# wiring.net
KiCad netlist of a schematic drawn in EAGLE
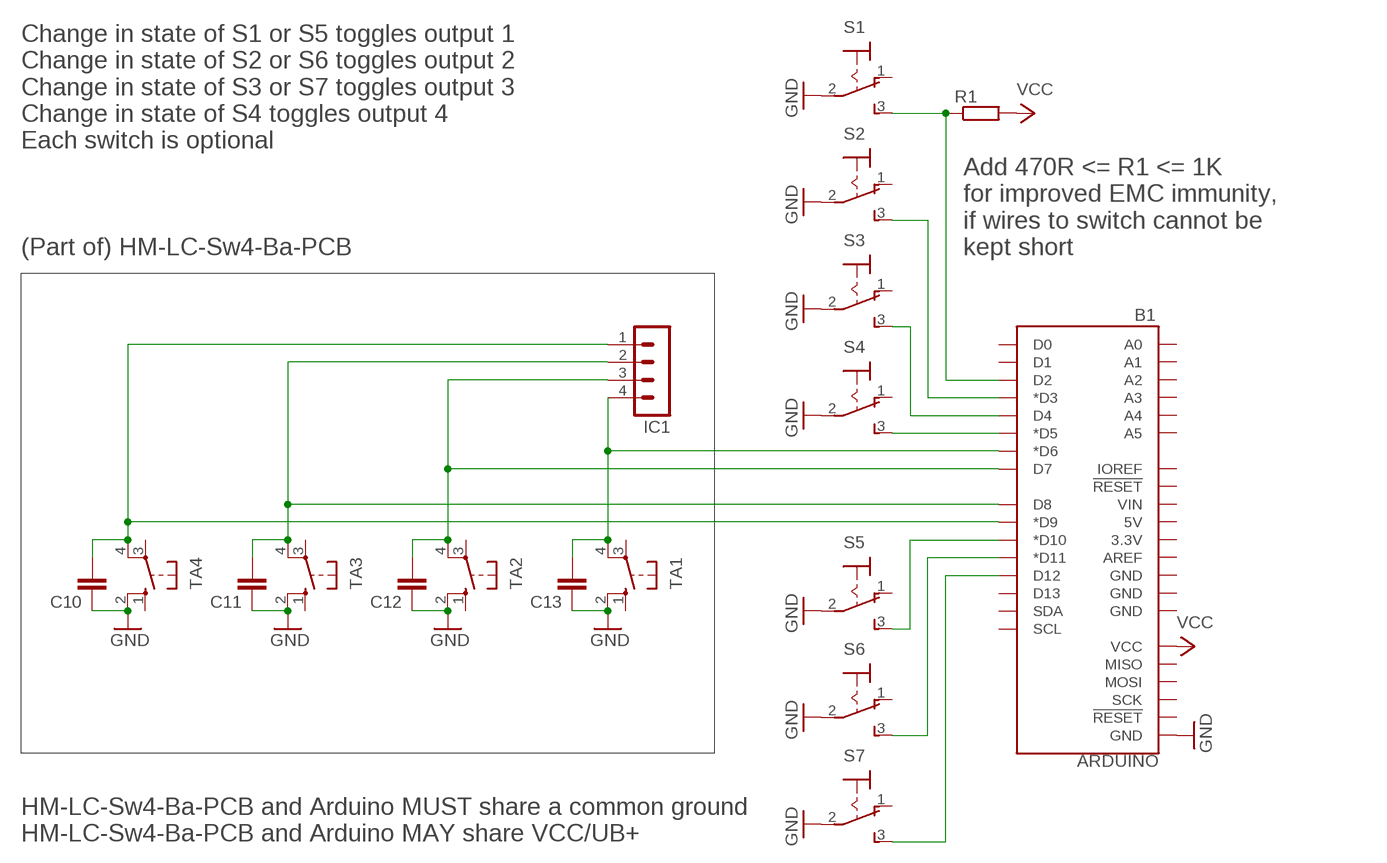
[diagram p0: schematic, sheet 1]

(export (version "E")
  (design (tool "Eeschema 10.0.6"))
  (components
    (comp (ref "B1")
      (value "ARDUINO")
      (footprint "eagle-import:ARDUINO_R3")
      (libsource (lib "eagle-import") (part "ARDUINO_UNO_R3"))
    )
    (comp (ref "C10")
      (value "C2,5-3")
      (footprint "eagle-import:C2.5-3")
      (libsource (lib "eagle-import") (part "C2,5-3"))
    )
    (comp (ref "C11")
      (value "C2,5-3")
      (footprint "eagle-import:C2.5-3")
      (libsource (lib "eagle-import") (part "C2,5-3"))
    )
    (comp (ref "C12")
      (value "C2,5-3")
      (footprint "eagle-import:C2.5-3")
      (libsource (lib "eagle-import") (part "C2,5-3"))
    )
    (comp (ref "C13")
      (value "C2,5-3")
      (footprint "eagle-import:C2.5-3")
      (libsource (lib "eagle-import") (part "C2,5-3"))
    )
    (comp (ref "IC1")
      (value "MA04-1")
      (footprint "eagle-import:MA04-1")
      (libsource (lib "eagle-import") (part "MA04-1"))
    )
    (comp (ref "R1")
      (value "R-EU_0204/5")
      (footprint "eagle-import:0204_5")
      (libsource (lib "eagle-import") (part "R-EU_0204/5"))
    )
    (comp (ref "S1")
      (value "320-916")
      (footprint "eagle-import:320-916")
      (libsource (lib "eagle-import") (part "320-916"))
    )
    (comp (ref "S2")
      (value "320-916")
      (footprint "eagle-import:320-916")
      (libsource (lib "eagle-import") (part "320-916"))
    )
    (comp (ref "S3")
      (value "320-916")
      (footprint "eagle-import:320-916")
      (libsource (lib "eagle-import") (part "320-916"))
    )
    (comp (ref "S4")
      (value "320-916")
      (footprint "eagle-import:320-916")
      (libsource (lib "eagle-import") (part "320-916"))
    )
    (comp (ref "S5")
      (value "320-916")
      (footprint "eagle-import:320-916")
      (libsource (lib "eagle-import") (part "320-916"))
    )
    (comp (ref "S6")
      (value "320-916")
      (footprint "eagle-import:320-916")
      (libsource (lib "eagle-import") (part "320-916"))
    )
    (comp (ref "S7")
      (value "320-916")
      (footprint "eagle-import:320-916")
      (libsource (lib "eagle-import") (part "320-916"))
    )
    (comp (ref "TA1")
      (value "10-XX")
      (footprint "eagle-import:B3F-10XX")
      (fields (field (name "MPN") "B3F-1000"))
      (libsource (lib "eagle-import") (part "10-XX"))
    )
    (comp (ref "TA2")
      (value "10-XX")
      (footprint "eagle-import:B3F-10XX")
      (fields (field (name "MPN") "B3F-1000"))
      (libsource (lib "eagle-import") (part "10-XX"))
    )
    (comp (ref "TA3")
      (value "10-XX")
      (footprint "eagle-import:B3F-10XX")
      (fields (field (name "MPN") "B3F-1000"))
      (libsource (lib "eagle-import") (part "10-XX"))
    )
    (comp (ref "TA4")
      (value "10-XX")
      (footprint "eagle-import:B3F-10XX")
      (fields (field (name "MPN") "B3F-1000"))
      (libsource (lib "eagle-import") (part "10-XX"))
    )
  )
  (nets
    (net (code "1") (name "GND") (class "Default")
      (node (ref "B1") (pin "GND@1") (pinfunction "GND_GND@1") (pintype "bidirectional"))
      (node (ref "C10") (pin "1") (pinfunction "1_1") (pintype "passive"))
      (node (ref "C11") (pin "1") (pinfunction "1_1") (pintype "passive"))
      (node (ref "C12") (pin "1") (pinfunction "1_1") (pintype "passive"))
      (node (ref "C13") (pin "1") (pinfunction "1_1") (pintype "passive"))
      (node (ref "S1") (pin "2") (pinfunction "P_2") (pintype "passive"))
      (node (ref "S2") (pin "2") (pinfunction "P_2") (pintype "passive"))
      (node (ref "S3") (pin "2") (pinfunction "P_2") (pintype "passive"))
      (node (ref "S4") (pin "2") (pinfunction "P_2") (pintype "passive"))
      (node (ref "S5") (pin "2") (pinfunction "P_2") (pintype "passive"))
      (node (ref "S6") (pin "2") (pinfunction "P_2") (pintype "passive"))
      (node (ref "S7") (pin "2") (pinfunction "P_2") (pintype "passive"))
      (node (ref "TA1") (pin "2") (pinfunction "S1_2") (pintype "passive"))
      (node (ref "TA2") (pin "2") (pinfunction "S1_2") (pintype "passive"))
      (node (ref "TA3") (pin "2") (pinfunction "S1_2") (pintype "passive"))
      (node (ref "TA4") (pin "2") (pinfunction "S1_2") (pintype "passive"))
    )
    (net (code "2") (name "Net-(B1-*D3)") (class "Default")
      (node (ref "B1") (pin "D3") (pinfunction "*D3_D3") (pintype "bidirectional"))
      (node (ref "S2") (pin "3") (pinfunction "S_3") (pintype "passive"))
    )
    (net (code "3") (name "Net-(B1-*D5)") (class "Default")
      (node (ref "B1") (pin "D5") (pinfunction "*D5_D5") (pintype "bidirectional"))
      (node (ref "S4") (pin "3") (pinfunction "S_3") (pintype "passive"))
    )
    (net (code "4") (name "Net-(B1-*D6)") (class "Default")
      (node (ref "B1") (pin "D6") (pinfunction "*D6_D6") (pintype "bidirectional"))
      (node (ref "C13") (pin "2") (pinfunction "2_2") (pintype "passive"))
      (node (ref "IC1") (pin "4") (pinfunction "4_4") (pintype "passive"))
      (node (ref "TA1") (pin "4") (pinfunction "P1_4") (pintype "passive"))
    )
    (net (code "5") (name "Net-(B1-*D9)") (class "Default")
      (node (ref "B1") (pin "D9") (pinfunction "*D9_D9") (pintype "bidirectional"))
      (node (ref "C10") (pin "2") (pinfunction "2_2") (pintype "passive"))
      (node (ref "IC1") (pin "1") (pinfunction "1_1") (pintype "passive"))
      (node (ref "TA4") (pin "4") (pinfunction "P1_4") (pintype "passive"))
    )
    (net (code "6") (name "Net-(B1-*D10)") (class "Default")
      (node (ref "B1") (pin "D10") (pinfunction "*D10_D10") (pintype "bidirectional"))
      (node (ref "S5") (pin "3") (pinfunction "S_3") (pintype "passive"))
    )
    (net (code "7") (name "Net-(B1-*D11)") (class "Default")
      (node (ref "B1") (pin "D11") (pinfunction "*D11_D11") (pintype "bidirectional"))
      (node (ref "S6") (pin "3") (pinfunction "S_3") (pintype "passive"))
    )
    (net (code "8") (name "Net-(S1-S)") (class "Default")
      (node (ref "B1") (pin "D2") (pinfunction "D2_D2") (pintype "bidirectional"))
      (node (ref "R1") (pin "1") (pinfunction "1_1") (pintype "passive"))
      (node (ref "S1") (pin "3") (pinfunction "S_3") (pintype "passive"))
    )
    (net (code "9") (name "Net-(S3-S)") (class "Default")
      (node (ref "B1") (pin "D4") (pinfunction "D4_D4") (pintype "bidirectional"))
      (node (ref "S3") (pin "3") (pinfunction "S_3") (pintype "passive"))
    )
    (net (code "10") (name "Net-(S7-S)") (class "Default")
      (node (ref "B1") (pin "D12") (pinfunction "D12_D12") (pintype "bidirectional"))
      (node (ref "S7") (pin "3") (pinfunction "S_3") (pintype "passive"))
    )
    (net (code "11") (name "Net-(TA2-P1)") (class "Default")
      (node (ref "B1") (pin "D7") (pinfunction "D7_D7") (pintype "bidirectional"))
      (node (ref "C12") (pin "2") (pinfunction "2_2") (pintype "passive"))
      (node (ref "IC1") (pin "3") (pinfunction "3_3") (pintype "passive"))
      (node (ref "TA2") (pin "4") (pinfunction "P1_4") (pintype "passive"))
    )
    (net (code "12") (name "Net-(TA3-P1)") (class "Default")
      (node (ref "B1") (pin "D8") (pinfunction "D8_D8") (pintype "bidirectional"))
      (node (ref "C11") (pin "2") (pinfunction "2_2") (pintype "passive"))
      (node (ref "IC1") (pin "2") (pinfunction "2_2") (pintype "passive"))
      (node (ref "TA3") (pin "4") (pinfunction "P1_4") (pintype "passive"))
    )
    (net (code "13") (name "VCC") (class "Default")
      (node (ref "B1") (pin "VCC") (pinfunction "VCC_VCC") (pintype "bidirectional"))
      (node (ref "R1") (pin "2") (pinfunction "2_2") (pintype "passive"))
    )
    (net (code "14") (name "unconnected-(B1-GND-PadGND@2)") (class "Default")
      (node (ref "B1") (pin "GND@2") (pinfunction "GND_GND@2") (pintype "bidirectional"))
    )
    (net (code "15") (name "unconnected-(B1-GND-PadGND@3)") (class "Default")
      (node (ref "B1") (pin "GND@3") (pinfunction "GND_GND@3") (pintype "bidirectional"))
    )
    (net (code "16") (name "unconnected-(B1-GND-PadGND@4)") (class "Default")
      (node (ref "B1") (pin "GND@4") (pinfunction "GND_GND@4") (pintype "bidirectional"))
    )
    (net (code "17") (name "unconnected-(B1-Pad3.3V)") (class "Default")
      (node (ref "B1") (pin "3.3V") (pinfunction "3.3V_3.3V") (pintype "bidirectional"))
    )
    (net (code "18") (name "unconnected-(B1-Pad5V)") (class "Default")
      (node (ref "B1") (pin "5V") (pinfunction "5V_5V") (pintype "bidirectional"))
    )
    (net (code "19") (name "unconnected-(B1-PadA0)") (class "Default")
      (node (ref "B1") (pin "A0") (pinfunction "A0_A0") (pintype "bidirectional"))
    )
    (net (code "20") (name "unconnected-(B1-PadA1)") (class "Default")
      (node (ref "B1") (pin "A1") (pinfunction "A1_A1") (pintype "bidirectional"))
    )
    (net (code "21") (name "unconnected-(B1-PadA2)") (class "Default")
      (node (ref "B1") (pin "A2") (pinfunction "A2_A2") (pintype "bidirectional"))
    )
    (net (code "22") (name "unconnected-(B1-PadA3)") (class "Default")
      (node (ref "B1") (pin "A3") (pinfunction "A3_A3") (pintype "bidirectional"))
    )
    (net (code "23") (name "unconnected-(B1-PadA4)") (class "Default")
      (node (ref "B1") (pin "A4") (pinfunction "A4_A4") (pintype "bidirectional"))
    )
    (net (code "24") (name "unconnected-(B1-PadA5)") (class "Default")
      (node (ref "B1") (pin "A5") (pinfunction "A5_A5") (pintype "bidirectional"))
    )
    (net (code "25") (name "unconnected-(B1-PadAREF)") (class "Default")
      (node (ref "B1") (pin "AREF") (pinfunction "AREF_AREF") (pintype "bidirectional"))
    )
    (net (code "26") (name "unconnected-(B1-PadD0)") (class "Default")
      (node (ref "B1") (pin "D0") (pinfunction "D0_D0") (pintype "bidirectional"))
    )
    (net (code "27") (name "unconnected-(B1-PadD1)") (class "Default")
      (node (ref "B1") (pin "D1") (pinfunction "D1_D1") (pintype "bidirectional"))
    )
    (net (code "28") (name "unconnected-(B1-PadD13)") (class "Default")
      (node (ref "B1") (pin "D13") (pinfunction "D13_D13") (pintype "bidirectional"))
    )
    (net (code "29") (name "unconnected-(B1-PadIOREF)") (class "Default")
      (node (ref "B1") (pin "IOREF") (pinfunction "IOREF_IOREF") (pintype "bidirectional"))
    )
    (net (code "30") (name "unconnected-(B1-PadMISO)") (class "Default")
      (node (ref "B1") (pin "MISO") (pinfunction "MISO_MISO") (pintype "bidirectional"))
    )
    (net (code "31") (name "unconnected-(B1-PadMOSI)") (class "Default")
      (node (ref "B1") (pin "MOSI") (pinfunction "MOSI_MOSI") (pintype "bidirectional"))
    )
    (net (code "32") (name "unconnected-(B1-PadSCK)") (class "Default")
      (node (ref "B1") (pin "SCK") (pinfunction "SCK_SCK") (pintype "bidirectional"))
    )
    (net (code "33") (name "unconnected-(B1-PadSCL)") (class "Default")
      (node (ref "B1") (pin "SCL") (pinfunction "SCL_SCL") (pintype "bidirectional"))
    )
    (net (code "34") (name "unconnected-(B1-PadSDA)") (class "Default")
      (node (ref "B1") (pin "SDA") (pinfunction "SDA_SDA") (pintype "bidirectional"))
    )
    (net (code "35") (name "unconnected-(B1-PadVIN)") (class "Default")
      (node (ref "B1") (pin "VIN") (pinfunction "VIN_VIN") (pintype "bidirectional"))
    )
    (net (code "36") (name "unconnected-(B1-~{RESET}-PadRESET@1)") (class "Default")
      (node (ref "B1") (pin "RESET@1") (pinfunction "~{RESET}_RESET@1") (pintype "bidirectional"))
    )
    (net (code "37") (name "unconnected-(B1-~{RESET}-PadRESET@2)") (class "Default")
      (node (ref "B1") (pin "RESET@2") (pinfunction "~{RESET}_RESET@2") (pintype "bidirectional"))
    )
    (net (code "38") (name "unconnected-(S1-O-Pad1)") (class "Default")
      (node (ref "S1") (pin "1") (pinfunction "O_1") (pintype "passive"))
    )
    (net (code "39") (name "unconnected-(S2-O-Pad1)") (class "Default")
      (node (ref "S2") (pin "1") (pinfunction "O_1") (pintype "passive"))
    )
    (net (code "40") (name "unconnected-(S3-O-Pad1)") (class "Default")
      (node (ref "S3") (pin "1") (pinfunction "O_1") (pintype "passive"))
    )
    (net (code "41") (name "unconnected-(S4-O-Pad1)") (class "Default")
      (node (ref "S4") (pin "1") (pinfunction "O_1") (pintype "passive"))
    )
    (net (code "42") (name "unconnected-(S5-O-Pad1)") (class "Default")
      (node (ref "S5") (pin "1") (pinfunction "O_1") (pintype "passive"))
    )
    (net (code "43") (name "unconnected-(S6-O-Pad1)") (class "Default")
      (node (ref "S6") (pin "1") (pinfunction "O_1") (pintype "passive"))
    )
    (net (code "44") (name "unconnected-(S7-O-Pad1)") (class "Default")
      (node (ref "S7") (pin "1") (pinfunction "O_1") (pintype "passive"))
    )
    (net (code "45") (name "unconnected-(TA1-P-Pad3)") (class "Default")
      (node (ref "TA1") (pin "3") (pinfunction "P_3") (pintype "passive"))
    )
    (net (code "46") (name "unconnected-(TA1-S-Pad1)") (class "Default")
      (node (ref "TA1") (pin "1") (pinfunction "S_1") (pintype "passive"))
    )
    (net (code "47") (name "unconnected-(TA2-P-Pad3)") (class "Default")
      (node (ref "TA2") (pin "3") (pinfunction "P_3") (pintype "passive"))
    )
    (net (code "48") (name "unconnected-(TA2-S-Pad1)") (class "Default")
      (node (ref "TA2") (pin "1") (pinfunction "S_1") (pintype "passive"))
    )
    (net (code "49") (name "unconnected-(TA3-P-Pad3)") (class "Default")
      (node (ref "TA3") (pin "3") (pinfunction "P_3") (pintype "passive"))
    )
    (net (code "50") (name "unconnected-(TA3-S-Pad1)") (class "Default")
      (node (ref "TA3") (pin "1") (pinfunction "S_1") (pintype "passive"))
    )
    (net (code "51") (name "unconnected-(TA4-P-Pad3)") (class "Default")
      (node (ref "TA4") (pin "3") (pinfunction "P_3") (pintype "passive"))
    )
    (net (code "52") (name "unconnected-(TA4-S-Pad1)") (class "Default")
      (node (ref "TA4") (pin "1") (pinfunction "S_1") (pintype "passive"))
    )
  )
)
